# ETHERNET.net
KiCad netlist of a schematic drawn in Altium Designer
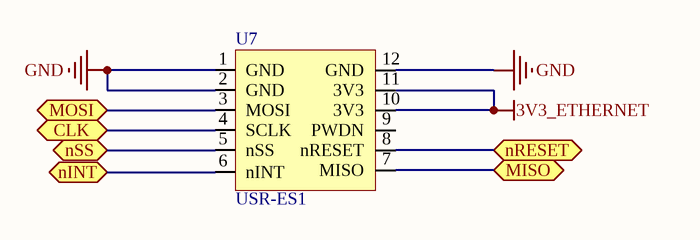
[diagram p0: ETHERNET.SchDoc]

(export (version "E")
  (design (tool "Eeschema 10.0.6"))
  (components
    (comp (ref "U7")
      (value "USR-ES1")
      (footprint "USR-ES1")
      (description "Ethernet module")
      (libsource (lib "CMN") (part "USR-ES1"))
    )
  )
  (nets
    (net (code "1") (name "/CLK") (class "Default")
      (node (ref "U7") (pin "4") (pinfunction "SCLK_4") (pintype "passive"))
    )
    (net (code "2") (name "/MISO") (class "Default")
      (node (ref "U7") (pin "7") (pinfunction "MISO_7") (pintype "passive"))
    )
    (net (code "3") (name "/MOSI") (class "Default")
      (node (ref "U7") (pin "3") (pinfunction "MOSI_3") (pintype "passive"))
    )
    (net (code "4") (name "/nINT") (class "Default")
      (node (ref "U7") (pin "6") (pinfunction "nINT_6") (pintype "passive"))
    )
    (net (code "5") (name "/nRESET") (class "Default")
      (node (ref "U7") (pin "8") (pinfunction "nRESET_8") (pintype "passive"))
    )
    (net (code "6") (name "/nSS") (class "Default")
      (node (ref "U7") (pin "5") (pinfunction "nSS_5") (pintype "passive"))
    )
    (net (code "7") (name "3V3_ETHERNET") (class "Default")
      (node (ref "U7") (pin "10") (pinfunction "3V3_10") (pintype "passive"))
      (node (ref "U7") (pin "11") (pinfunction "3V3_11") (pintype "passive"))
    )
    (net (code "8") (name "GND") (class "Default")
      (node (ref "U7") (pin "1") (pinfunction "GND_1") (pintype "passive"))
      (node (ref "U7") (pin "12") (pinfunction "GND_12") (pintype "passive"))
      (node (ref "U7") (pin "2") (pinfunction "GND_2") (pintype "passive"))
    )
    (net (code "9") (name "unconnected-(U7-PWDN-Pad9)") (class "Default")
      (node (ref "U7") (pin "9") (pinfunction "PWDN_9") (pintype "passive"))
    )
  )
)
